# 02-FPGA_IO_MIPI_TS.net
KiCad netlist of a schematic drawn in Altium Designer
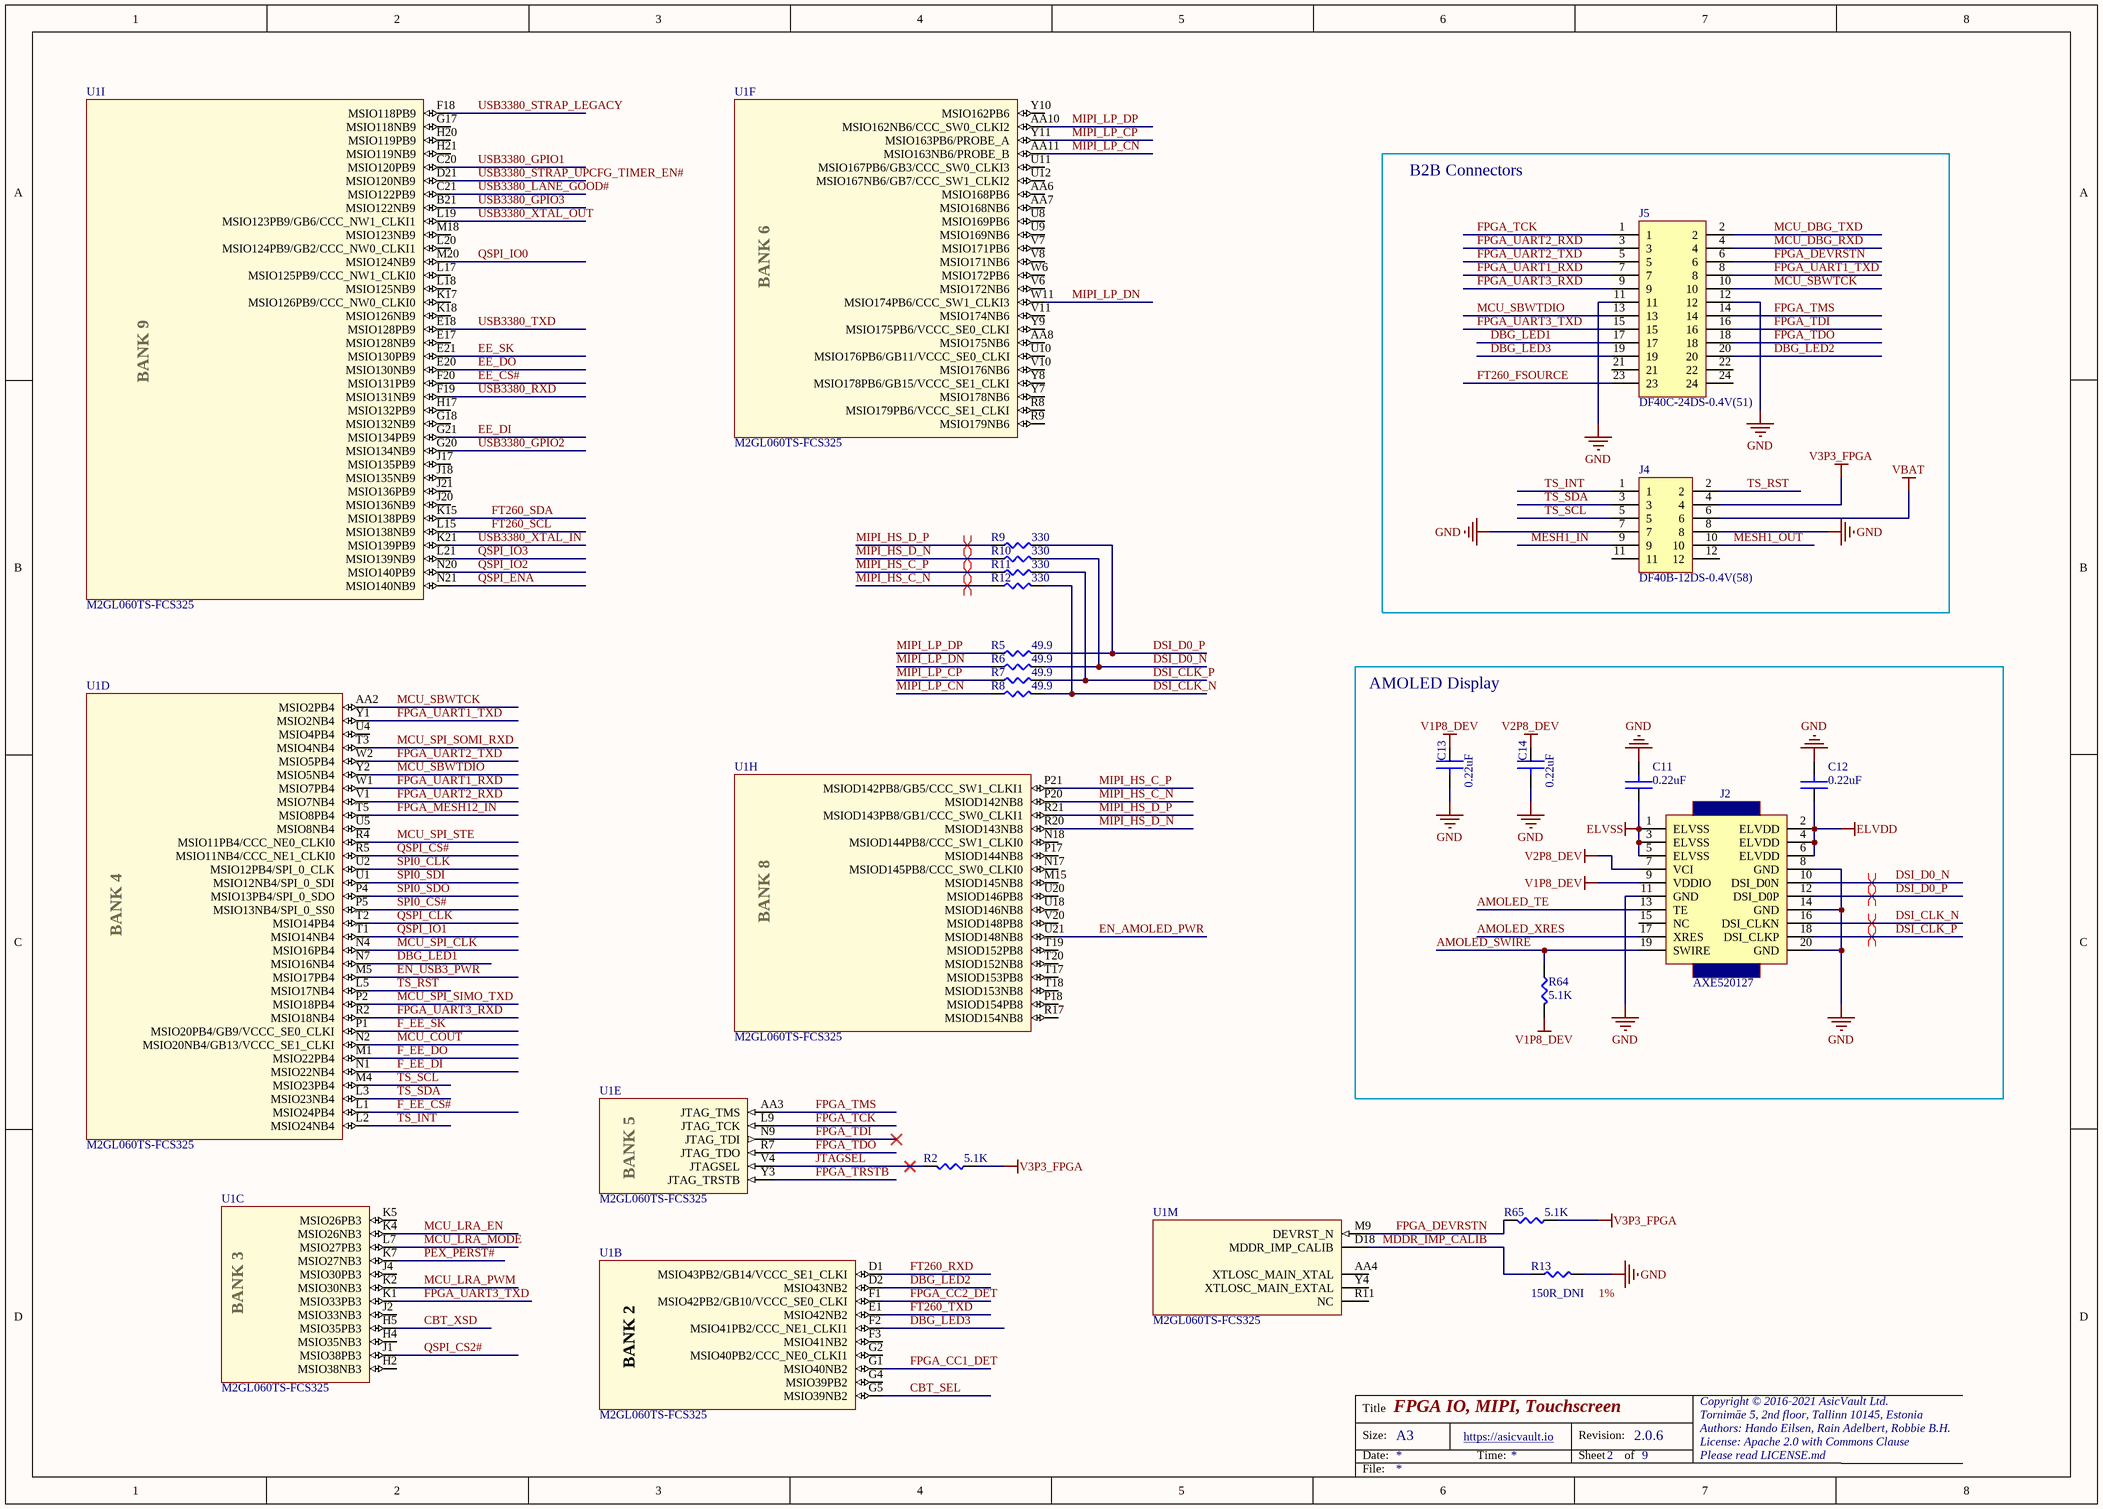
[diagram p0: 02-FPGA_IO_MIPI_TS.SchDoc]

(export (version "E")
  (design (tool "Eeschema 10.0.6"))
  (components
    (comp (ref "C11") (value "0.22uF") (footprint "C0201") (libsource (lib "AMOLED") (part "0.22uF/0201")))
    (comp (ref "C12") (value "0.22uF") (footprint "C0201") (libsource (lib "AMOLED") (part "0.22uF/0201")))
    (comp (ref "C13") (value "0.22uF") (footprint "C0201") (libsource (lib "AMOLED") (part "0.22uF/0201")))
    (comp (ref "C14") (value "0.22uF") (footprint "C0201") (libsource (lib "AMOLED") (part "0.22uF/0201")))
    (comp (ref "J2")
      (value "AXE520127")
      (footprint "AXE520127")
      (libsource (lib "AMOLED") (part "AXE520127"))
    )
    (comp (ref "J4")
      (value "DF40B-12DS-0.4V(58)")
      (footprint "DF40B-12DS")
      (libsource (lib "AMOLED") (part "DF40B-12DS-0.4V(58)"))
    )
    (comp (ref "J5")
      (value "DF40C-24DS-0.4V(51)")
      (footprint "DF40C-24DS")
      (libsource (lib "AMOLED") (part "DF40C-24DS-0.4V(51)"))
    )
    (comp (ref "R2")
      (value "5.1K")
      (footprint "R0201")
      (libsource (lib "Control_Board") (part "5.1K/1%/0201"))
    )
    (comp (ref "R5")
      (value "49.9")
      (footprint "R0201")
      (libsource (lib "Control_Board") (part "49.9/1%/0201"))
    )
    (comp (ref "R6")
      (value "49.9")
      (footprint "R0201")
      (libsource (lib "Control_Board") (part "49.9/1%/0201"))
    )
    (comp (ref "R7")
      (value "49.9")
      (footprint "R0201")
      (libsource (lib "Control_Board") (part "49.9/1%/0201"))
    )
    (comp (ref "R8")
      (value "49.9")
      (footprint "R0201")
      (libsource (lib "Control_Board") (part "49.9/1%/0201"))
    )
    (comp (ref "R9") (value "330") (footprint "R0201") (libsource (lib "Control_Board") (part "330/1%/0201")))
    (comp (ref "R10")
      (value "330")
      (footprint "R0201")
      (libsource (lib "Control_Board") (part "330/1%/0201"))
    )
    (comp (ref "R11")
      (value "330")
      (footprint "R0201")
      (libsource (lib "Control_Board") (part "330/1%/0201"))
    )
    (comp (ref "R12")
      (value "330")
      (footprint "R0201")
      (libsource (lib "Control_Board") (part "330/1%/0201"))
    )
    (comp (ref "R13")
      (value "150R_DNI")
      (footprint "R0201")
      (libsource (lib "Control_Board") (part "150R/1%/0201"))
    )
    (comp (ref "R64")
      (value "5.1K")
      (footprint "R0201")
      (libsource (lib "Control_Board") (part "5.1K/1%/0201"))
    )
    (comp (ref "R65")
      (value "5.1K")
      (footprint "R0201")
      (libsource (lib "Control_Board") (part "5.1K/1%/0201"))
    )
    (comp (ref "U1")
      (value "M2GL060TS-FCS325")
      (footprint "FCS325-OPT1")
      (libsource (lib "Board3") (part "M2GL060TS-FCS325"))
    )
  )
  (nets
    (net (code "1") (name "/AMOLED_SWIRE") (class "Default")
      (node (ref "J2") (pin "19") (pinfunction "SWIRE_19") (pintype "passive"))
      (node (ref "R64") (pin "1") (pinfunction "1_1") (pintype "passive"))
    )
    (net (code "2") (name "/AMOLED_TE") (class "Default")
      (node (ref "J2") (pin "13") (pinfunction "TE_13") (pintype "passive"))
    )
    (net (code "3") (name "/AMOLED_XRES") (class "Default")
      (node (ref "J2") (pin "17") (pinfunction "XRES_17") (pintype "passive"))
    )
    (net (code "4") (name "/CBT_SEL") (class "Default")
      (node (ref "U1") (pin "G5") (pinfunction "MSIO39NB2_G5") (pintype "bidirectional"))
    )
    (net (code "5") (name "/CBT_XSD") (class "Default")
      (node (ref "U1") (pin "H5") (pinfunction "MSIO35PB3_H5") (pintype "bidirectional"))
    )
    (net (code "6") (name "/DBG_LED1") (class "Default")
      (node (ref "J5") (pin "17") (pinfunction "17_17") (pintype "passive"))
      (node (ref "U1") (pin "N7") (pinfunction "MSIO16NB4_N7") (pintype "bidirectional"))
    )
    (net (code "7") (name "/DBG_LED2") (class "Default")
      (node (ref "J5") (pin "20") (pinfunction "20_20") (pintype "passive"))
      (node (ref "U1") (pin "D2") (pinfunction "MSIO43NB2_D2") (pintype "bidirectional"))
    )
    (net (code "8") (name "/DBG_LED3") (class "Default")
      (node (ref "J5") (pin "19") (pinfunction "19_19") (pintype "passive"))
      (node (ref "U1") (pin "F2") (pinfunction "MSIO41PB2/CCC_NE1_CLKI1_F2") (pintype "bidirectional"))
    )
    (net (code "9") (name "/DSI_CLK_N") (class "Default")
      (node (ref "J2") (pin "16") (pinfunction "DSI_CLKN_16") (pintype "passive"))
      (node (ref "R12") (pin "2") (pinfunction "2_2") (pintype "passive"))
      (node (ref "R8") (pin "2") (pinfunction "2_2") (pintype "passive"))
    )
    (net (code "10") (name "/DSI_CLK_P") (class "Default")
      (node (ref "J2") (pin "18") (pinfunction "DSI_CLKP_18") (pintype "passive"))
      (node (ref "R11") (pin "2") (pinfunction "2_2") (pintype "passive"))
      (node (ref "R7") (pin "2") (pinfunction "2_2") (pintype "passive"))
    )
    (net (code "11") (name "/DSI_D0_N") (class "Default")
      (node (ref "J2") (pin "10") (pinfunction "DSI_D0N_10") (pintype "passive"))
      (node (ref "R10") (pin "2") (pinfunction "2_2") (pintype "passive"))
      (node (ref "R6") (pin "2") (pinfunction "2_2") (pintype "passive"))
    )
    (net (code "12") (name "/DSI_D0_P") (class "Default")
      (node (ref "J2") (pin "12") (pinfunction "DSI_D0P_12") (pintype "passive"))
      (node (ref "R5") (pin "2") (pinfunction "2_2") (pintype "passive"))
      (node (ref "R9") (pin "2") (pinfunction "2_2") (pintype "passive"))
    )
    (net (code "13") (name "/EE_CS#") (class "Default")
      (node (ref "U1") (pin "F20") (pinfunction "MSIO131PB9_F20") (pintype "bidirectional"))
    )
    (net (code "14") (name "/EE_DI") (class "Default")
      (node (ref "U1") (pin "G21") (pinfunction "MSIO134PB9_G21") (pintype "bidirectional"))
    )
    (net (code "15") (name "/EE_DO") (class "Default")
      (node (ref "U1") (pin "E20") (pinfunction "MSIO130NB9_E20") (pintype "bidirectional"))
    )
    (net (code "16") (name "/EE_SK") (class "Default")
      (node (ref "U1") (pin "E21") (pinfunction "MSIO130PB9_E21") (pintype "bidirectional"))
    )
    (net (code "17") (name "/EN_AMOLED_PWR") (class "Default")
      (node (ref "U1") (pin "U21") (pinfunction "MSIOD148NB8_U21") (pintype "bidirectional"))
    )
    (net (code "18") (name "/EN_USB3_PWR") (class "Default")
      (node (ref "U1") (pin "M5") (pinfunction "MSIO17PB4_M5") (pintype "bidirectional"))
    )
    (net (code "19") (name "/FPGA_CC1_DET") (class "Default")
      (node (ref "U1") (pin "G1") (pinfunction "MSIO40NB2_G1") (pintype "bidirectional"))
    )
    (net (code "20") (name "/FPGA_CC2_DET") (class "Default")
      (node (ref "U1") (pin "F1") (pinfunction "MSIO42PB2/GB10/VCCC_SE0_CLKI_F1") (pintype "bidirectional"))
    )
    (net (code "21") (name "/FPGA_DEVRSTN") (class "Default")
      (node (ref "J5") (pin "6") (pinfunction "6_6") (pintype "passive"))
      (node (ref "R65") (pin "2") (pinfunction "2_2") (pintype "passive"))
      (node (ref "U1") (pin "M9") (pinfunction "DEVRST_N_M9") (pintype "input"))
    )
    (net (code "22") (name "/FPGA_MESH12_IN") (class "Default")
      (node (ref "U1") (pin "T5") (pinfunction "MSIO8PB4_T5") (pintype "bidirectional"))
    )
    (net (code "23") (name "/FPGA_TCK") (class "Default")
      (node (ref "J5") (pin "1") (pinfunction "1_1") (pintype "passive"))
      (node (ref "U1") (pin "L9") (pinfunction "JTAG_TCK_L9") (pintype "input"))
    )
    (net (code "24") (name "/FPGA_TDI") (class "Default")
      (node (ref "J5") (pin "16") (pinfunction "16_16") (pintype "passive"))
      (node (ref "U1") (pin "N9") (pinfunction "JTAG_TDI_N9") (pintype "output"))
    )
    (net (code "25") (name "/FPGA_TDO") (class "Default")
      (node (ref "J5") (pin "18") (pinfunction "18_18") (pintype "passive"))
      (node (ref "U1") (pin "R7") (pinfunction "JTAG_TDO_R7") (pintype "input"))
    )
    (net (code "26") (name "/FPGA_TMS") (class "Default")
      (node (ref "J5") (pin "14") (pinfunction "14_14") (pintype "passive"))
      (node (ref "U1") (pin "AA3") (pinfunction "JTAG_TMS_AA3") (pintype "input"))
    )
    (net (code "27") (name "/FPGA_TRSTB") (class "Default")
      (node (ref "U1") (pin "Y3") (pinfunction "JTAG_TRSTB_Y3") (pintype "input"))
    )
    (net (code "28") (name "/FPGA_UART1_RXD") (class "Default")
      (node (ref "J5") (pin "7") (pinfunction "7_7") (pintype "passive"))
      (node (ref "U1") (pin "W1") (pinfunction "MSIO7PB4_W1") (pintype "bidirectional"))
    )
    (net (code "29") (name "/FPGA_UART1_TXD") (class "Default")
      (node (ref "J5") (pin "8") (pinfunction "8_8") (pintype "passive"))
      (node (ref "U1") (pin "Y1") (pinfunction "MSIO2NB4_Y1") (pintype "bidirectional"))
    )
    (net (code "30") (name "/FPGA_UART2_RXD") (class "Default")
      (node (ref "J5") (pin "3") (pinfunction "3_3") (pintype "passive"))
      (node (ref "U1") (pin "V1") (pinfunction "MSIO7NB4_V1") (pintype "bidirectional"))
    )
    (net (code "31") (name "/FPGA_UART2_TXD") (class "Default")
      (node (ref "J5") (pin "5") (pinfunction "5_5") (pintype "passive"))
      (node (ref "U1") (pin "W2") (pinfunction "MSIO5PB4_W2") (pintype "bidirectional"))
    )
    (net (code "32") (name "/FPGA_UART3_RXD") (class "Default")
      (node (ref "J5") (pin "9") (pinfunction "9_9") (pintype "passive"))
      (node (ref "U1") (pin "R2") (pinfunction "MSIO18NB4_R2") (pintype "bidirectional"))
    )
    (net (code "33") (name "/FPGA_UART3_TXD") (class "Default")
      (node (ref "J5") (pin "15") (pinfunction "15_15") (pintype "passive"))
      (node (ref "U1") (pin "K1") (pinfunction "MSIO33PB3_K1") (pintype "bidirectional"))
    )
    (net (code "34") (name "/FT260_FSOURCE") (class "Default")
      (node (ref "J5") (pin "23") (pinfunction "23_23") (pintype "passive"))
    )
    (net (code "35") (name "/FT260_RXD") (class "Default")
      (node (ref "U1") (pin "D1") (pinfunction "MSIO43PB2/GB14/VCCC_SE1_CLKI_D1") (pintype "bidirectional"))
    )
    (net (code "36") (name "/FT260_SCL") (class "Default")
      (node (ref "U1") (pin "L15") (pinfunction "MSIO138NB9_L15") (pintype "bidirectional"))
    )
    (net (code "37") (name "/FT260_SDA") (class "Default")
      (node (ref "U1") (pin "K15") (pinfunction "MSIO138PB9_K15") (pintype "bidirectional"))
    )
    (net (code "38") (name "/FT260_TXD") (class "Default")
      (node (ref "U1") (pin "E1") (pinfunction "MSIO42NB2_E1") (pintype "bidirectional"))
    )
    (net (code "39") (name "/F_EE_CS#") (class "Default")
      (node (ref "U1") (pin "L1") (pinfunction "MSIO24PB4_L1") (pintype "bidirectional"))
    )
    (net (code "40") (name "/F_EE_DI") (class "Default")
      (node (ref "U1") (pin "N1") (pinfunction "MSIO22NB4_N1") (pintype "bidirectional"))
    )
    (net (code "41") (name "/F_EE_DO") (class "Default")
      (node (ref "U1") (pin "M1") (pinfunction "MSIO22PB4_M1") (pintype "bidirectional"))
    )
    (net (code "42") (name "/F_EE_SK") (class "Default")
      (node (ref "U1") (pin "P1") (pinfunction "MSIO20PB4/GB9/VCCC_SE0_CLKI_P1") (pintype "bidirectional"))
    )
    (net (code "43") (name "/JTAGSEL") (class "Default")
      (node (ref "R2") (pin "2") (pinfunction "2_2") (pintype "passive"))
      (node (ref "U1") (pin "V4") (pinfunction "JTAGSEL_V4") (pintype "input"))
    )
    (net (code "44") (name "/MCU_COUT") (class "Default")
      (node (ref "U1") (pin "N2") (pinfunction "MSIO20NB4/GB13/VCCC_SE1_CLKI_N2") (pintype "bidirectional"))
    )
    (net (code "45") (name "/MCU_DBG_RXD") (class "Default")
      (node (ref "J5") (pin "4") (pinfunction "4_4") (pintype "passive"))
    )
    (net (code "46") (name "/MCU_DBG_TXD") (class "Default")
      (node (ref "J5") (pin "2") (pinfunction "2_2") (pintype "passive"))
    )
    (net (code "47") (name "/MCU_LRA_EN") (class "Default")
      (node (ref "U1") (pin "K4") (pinfunction "MSIO26NB3_K4") (pintype "bidirectional"))
    )
    (net (code "48") (name "/MCU_LRA_MODE") (class "Default")
      (node (ref "U1") (pin "L7") (pinfunction "MSIO27PB3_L7") (pintype "bidirectional"))
    )
    (net (code "49") (name "/MCU_LRA_PWM") (class "Default")
      (node (ref "U1") (pin "K2") (pinfunction "MSIO30NB3_K2") (pintype "bidirectional"))
    )
    (net (code "50") (name "/MCU_SBWTCK") (class "Default")
      (node (ref "J5") (pin "10") (pinfunction "10_10") (pintype "passive"))
      (node (ref "U1") (pin "AA2") (pinfunction "MSIO2PB4_AA2") (pintype "bidirectional"))
    )
    (net (code "51") (name "/MCU_SBWTDIO") (class "Default")
      (node (ref "J5") (pin "13") (pinfunction "13_13") (pintype "passive"))
      (node (ref "U1") (pin "Y2") (pinfunction "MSIO5NB4_Y2") (pintype "bidirectional"))
    )
    (net (code "52") (name "/MCU_SPI_CLK") (class "Default")
      (node (ref "U1") (pin "N4") (pinfunction "MSIO16PB4_N4") (pintype "bidirectional"))
    )
    (net (code "53") (name "/MCU_SPI_SIMO_TXD") (class "Default")
      (node (ref "U1") (pin "P2") (pinfunction "MSIO18PB4_P2") (pintype "bidirectional"))
    )
    (net (code "54") (name "/MCU_SPI_SOMI_RXD") (class "Default")
      (node (ref "U1") (pin "T3") (pinfunction "MSIO4NB4_T3") (pintype "bidirectional"))
    )
    (net (code "55") (name "/MCU_SPI_STE") (class "Default")
      (node (ref "U1") (pin "R4") (pinfunction "MSIO11PB4/CCC_NE0_CLKI0_R4") (pintype "bidirectional"))
    )
    (net (code "56") (name "/MDDR_IMP_CALIB") (class "Default")
      (node (ref "R13") (pin "1") (pinfunction "1_1") (pintype "passive"))
      (node (ref "U1") (pin "D18") (pinfunction "MDDR_IMP_CALIB_D18") (pintype "passive"))
    )
    (net (code "57") (name "/MESH1_IN") (class "Default")
      (node (ref "J4") (pin "9") (pinfunction "9_9") (pintype "passive"))
    )
    (net (code "58") (name "/MESH1_OUT") (class "Default")
      (node (ref "J4") (pin "10") (pinfunction "10_10") (pintype "passive"))
    )
    (net (code "59") (name "/MIPI_HS_C_N") (class "Default")
      (node (ref "R12") (pin "1") (pinfunction "1_1") (pintype "passive"))
      (node (ref "U1") (pin "P20") (pinfunction "MSIOD142NB8_P20") (pintype "bidirectional"))
    )
    (net (code "60") (name "/MIPI_HS_C_P") (class "Default")
      (node (ref "R11") (pin "1") (pinfunction "1_1") (pintype "passive"))
      (node (ref "U1") (pin "P21") (pinfunction "MSIOD142PB8/GB5/CCC_SW1_CLKI1_P21") (pintype "bidirectional"))
    )
    (net (code "61") (name "/MIPI_HS_D_N") (class "Default")
      (node (ref "R10") (pin "1") (pinfunction "1_1") (pintype "passive"))
      (node (ref "U1") (pin "R20") (pinfunction "MSIOD143NB8_R20") (pintype "bidirectional"))
    )
    (net (code "62") (name "/MIPI_HS_D_P") (class "Default")
      (node (ref "R9") (pin "1") (pinfunction "1_1") (pintype "passive"))
      (node (ref "U1") (pin "R21") (pinfunction "MSIOD143PB8/GB1/CCC_SW0_CLKI1_R21") (pintype "bidirectional"))
    )
    (net (code "63") (name "/MIPI_LP_CN") (class "Default")
      (node (ref "R8") (pin "1") (pinfunction "1_1") (pintype "passive"))
      (node (ref "U1") (pin "AA11") (pinfunction "MSIO163NB6/PROBE_B_AA11") (pintype "bidirectional"))
    )
    (net (code "64") (name "/MIPI_LP_CP") (class "Default")
      (node (ref "R7") (pin "1") (pinfunction "1_1") (pintype "passive"))
      (node (ref "U1") (pin "Y11") (pinfunction "MSIO163PB6/PROBE_A_Y11") (pintype "bidirectional"))
    )
    (net (code "65") (name "/MIPI_LP_DN") (class "Default")
      (node (ref "R6") (pin "1") (pinfunction "1_1") (pintype "passive"))
      (node (ref "U1") (pin "W11") (pinfunction "MSIO174PB6/CCC_SW1_CLKI3_W11") (pintype "bidirectional"))
    )
    (net (code "66") (name "/MIPI_LP_DP") (class "Default")
      (node (ref "R5") (pin "1") (pinfunction "1_1") (pintype "passive"))
      (node (ref "U1") (pin "AA10") (pinfunction "MSIO162NB6/CCC_SW0_CLKI2_AA10") (pintype "bidirectional"))
    )
    (net (code "67") (name "/PEX_PERST#") (class "Default")
      (node (ref "U1") (pin "K7") (pinfunction "MSIO27NB3_K7") (pintype "bidirectional"))
    )
    (net (code "68") (name "/QSPI_CLK") (class "Default")
      (node (ref "U1") (pin "T2") (pinfunction "MSIO14PB4_T2") (pintype "bidirectional"))
    )
    (net (code "69") (name "/QSPI_CS#") (class "Default")
      (node (ref "U1") (pin "R5") (pinfunction "MSIO11NB4/CCC_NE1_CLKI0_R5") (pintype "bidirectional"))
    )
    (net (code "70") (name "/QSPI_CS2#") (class "Default")
      (node (ref "U1") (pin "J1") (pinfunction "MSIO38PB3_J1") (pintype "bidirectional"))
    )
    (net (code "71") (name "/QSPI_ENA") (class "Default")
      (node (ref "U1") (pin "N21") (pinfunction "MSIO140NB9_N21") (pintype "bidirectional"))
    )
    (net (code "72") (name "/QSPI_IO0") (class "Default")
      (node (ref "U1") (pin "M20") (pinfunction "MSIO124NB9_M20") (pintype "bidirectional"))
    )
    (net (code "73") (name "/QSPI_IO1") (class "Default")
      (node (ref "U1") (pin "T1") (pinfunction "MSIO14NB4_T1") (pintype "bidirectional"))
    )
    (net (code "74") (name "/QSPI_IO2") (class "Default")
      (node (ref "U1") (pin "N20") (pinfunction "MSIO140PB9_N20") (pintype "bidirectional"))
    )
    (net (code "75") (name "/QSPI_IO3") (class "Default")
      (node (ref "U1") (pin "L21") (pinfunction "MSIO139NB9_L21") (pintype "bidirectional"))
    )
    (net (code "76") (name "/SPI0_CLK") (class "Default")
      (node (ref "U1") (pin "U2") (pinfunction "MSIO12PB4/SPI_0_CLK_U2") (pintype "bidirectional"))
    )
    (net (code "77") (name "/SPI0_CS#") (class "Default")
      (node (ref "U1") (pin "P5") (pinfunction "MSIO13NB4/SPI_0_SS0_P5") (pintype "bidirectional"))
    )
    (net (code "78") (name "/SPI0_SDI") (class "Default")
      (node (ref "U1") (pin "U1") (pinfunction "MSIO12NB4/SPI_0_SDI_U1") (pintype "bidirectional"))
    )
    (net (code "79") (name "/SPI0_SDO") (class "Default")
      (node (ref "U1") (pin "P4") (pinfunction "MSIO13PB4/SPI_0_SDO_P4") (pintype "bidirectional"))
    )
    (net (code "80") (name "/TS_INT") (class "Default")
      (node (ref "J4") (pin "1") (pinfunction "1_1") (pintype "passive"))
      (node (ref "U1") (pin "L2") (pinfunction "MSIO24NB4_L2") (pintype "bidirectional"))
    )
    (net (code "81") (name "/TS_RST") (class "Default")
      (node (ref "J4") (pin "2") (pinfunction "2_2") (pintype "passive"))
      (node (ref "U1") (pin "L5") (pinfunction "MSIO17NB4_L5") (pintype "bidirectional"))
    )
    (net (code "82") (name "/TS_SCL") (class "Default")
      (node (ref "J4") (pin "5") (pinfunction "5_5") (pintype "passive"))
      (node (ref "U1") (pin "M4") (pinfunction "MSIO23PB4_M4") (pintype "bidirectional"))
    )
    (net (code "83") (name "/TS_SDA") (class "Default")
      (node (ref "J4") (pin "3") (pinfunction "3_3") (pintype "passive"))
      (node (ref "U1") (pin "L3") (pinfunction "MSIO23NB4_L3") (pintype "bidirectional"))
    )
    (net (code "84") (name "/USB3380_GPIO1") (class "Default")
      (node (ref "U1") (pin "C20") (pinfunction "MSIO120PB9_C20") (pintype "bidirectional"))
    )
    (net (code "85") (name "/USB3380_GPIO2") (class "Default")
      (node (ref "U1") (pin "G20") (pinfunction "MSIO134NB9_G20") (pintype "bidirectional"))
    )
    (net (code "86") (name "/USB3380_GPIO3") (class "Default")
      (node (ref "U1") (pin "B21") (pinfunction "MSIO122NB9_B21") (pintype "bidirectional"))
    )
    (net (code "87") (name "/USB3380_LANE_GOOD#") (class "Default")
      (node (ref "U1") (pin "C21") (pinfunction "MSIO122PB9_C21") (pintype "bidirectional"))
    )
    (net (code "88") (name "/USB3380_RXD") (class "Default")
      (node (ref "U1") (pin "F19") (pinfunction "MSIO131NB9_F19") (pintype "bidirectional"))
    )
    (net (code "89") (name "/USB3380_STRAP_LEGACY") (class "Default")
      (node (ref "U1") (pin "F18") (pinfunction "MSIO118PB9_F18") (pintype "bidirectional"))
    )
    (net (code "90") (name "/USB3380_STRAP_UPCFG_TIMER_EN#") (class "Default")
      (node (ref "U1") (pin "D21") (pinfunction "MSIO120NB9_D21") (pintype "bidirectional"))
    )
    (net (code "91") (name "/USB3380_TXD") (class "Default")
      (node (ref "U1") (pin "E18") (pinfunction "MSIO128PB9_E18") (pintype "bidirectional"))
    )
    (net (code "92") (name "/USB3380_XTAL_IN") (class "Default")
      (node (ref "U1") (pin "K21") (pinfunction "MSIO139PB9_K21") (pintype "bidirectional"))
    )
    (net (code "93") (name "/USB3380_XTAL_OUT") (class "Default")
      (node (ref "U1") (pin "L19") (pinfunction "MSIO123PB9/GB6/CCC_NW1_CLKI1_L19") (pintype "bidirectional"))
    )
    (net (code "94") (name "ELVDD") (class "Default")
      (node (ref "C12") (pin "1") (pinfunction "1_1") (pintype "passive"))
      (node (ref "J2") (pin "2") (pinfunction "ELVDD_2") (pintype "passive"))
      (node (ref "J2") (pin "4") (pinfunction "ELVDD_4") (pintype "passive"))
      (node (ref "J2") (pin "6") (pinfunction "ELVDD_6") (pintype "passive"))
    )
    (net (code "95") (name "ELVSS") (class "Default")
      (node (ref "C11") (pin "1") (pinfunction "1_1") (pintype "passive"))
      (node (ref "J2") (pin "1") (pinfunction "ELVSS_1") (pintype "passive"))
      (node (ref "J2") (pin "3") (pinfunction "ELVSS_3") (pintype "passive"))
      (node (ref "J2") (pin "5") (pinfunction "ELVSS_5") (pintype "passive"))
    )
    (net (code "96") (name "GND") (class "Default")
      (node (ref "C11") (pin "2") (pinfunction "2_2") (pintype "passive"))
      (node (ref "C12") (pin "2") (pinfunction "2_2") (pintype "passive"))
      (node (ref "C13") (pin "2") (pinfunction "2_2") (pintype "passive"))
      (node (ref "C14") (pin "2") (pinfunction "2_2") (pintype "passive"))
      (node (ref "J2") (pin "11") (pinfunction "GND_11") (pintype "passive"))
      (node (ref "J2") (pin "14") (pinfunction "GND_14") (pintype "passive"))
      (node (ref "J2") (pin "20") (pinfunction "GND_20") (pintype "passive"))
      (node (ref "J2") (pin "8") (pinfunction "GND_8") (pintype "passive"))
      (node (ref "J4") (pin "7") (pinfunction "7_7") (pintype "passive"))
      (node (ref "J4") (pin "8") (pinfunction "8_8") (pintype "passive"))
      (node (ref "J5") (pin "11") (pinfunction "11_11") (pintype "passive"))
      (node (ref "J5") (pin "12") (pinfunction "12_12") (pintype "passive"))
      (node (ref "R13") (pin "2") (pinfunction "2_2") (pintype "passive"))
    )
    (net (code "97") (name "V1P8_DEV") (class "Default")
      (node (ref "C13") (pin "1") (pinfunction "1_1") (pintype "passive"))
      (node (ref "J2") (pin "9") (pinfunction "VDDIO_9") (pintype "passive"))
      (node (ref "R64") (pin "2") (pinfunction "2_2") (pintype "passive"))
    )
    (net (code "98") (name "V2P8_DEV") (class "Default")
      (node (ref "C14") (pin "1") (pinfunction "1_1") (pintype "passive"))
      (node (ref "J2") (pin "7") (pinfunction "VCI_7") (pintype "passive"))
    )
    (net (code "99") (name "V3P3_FPGA") (class "Default")
      (node (ref "J4") (pin "4") (pinfunction "4_4") (pintype "passive"))
      (node (ref "R2") (pin "1") (pinfunction "1_1") (pintype "passive"))
      (node (ref "R65") (pin "1") (pinfunction "1_1") (pintype "passive"))
    )
    (net (code "100") (name "VBAT") (class "Default")
      (node (ref "J4") (pin "6") (pinfunction "6_6") (pintype "passive"))
    )
    (net (code "101") (name "unconnected-(J2-NC-Pad15)") (class "Default")
      (node (ref "J2") (pin "15") (pinfunction "NC_15") (pintype "passive"))
    )
    (net (code "102") (name "unconnected-(J4-Pad11)") (class "Default")
      (node (ref "J4") (pin "11") (pinfunction "11_11") (pintype "passive"))
    )
    (net (code "103") (name "unconnected-(J4-Pad12)") (class "Default")
      (node (ref "J4") (pin "12") (pinfunction "12_12") (pintype "passive"))
    )
    (net (code "104") (name "unconnected-(J5-Pad21)") (class "Default")
      (node (ref "J5") (pin "21") (pinfunction "21_21") (pintype "passive"))
    )
    (net (code "105") (name "unconnected-(J5-Pad22)") (class "Default")
      (node (ref "J5") (pin "22") (pinfunction "22_22") (pintype "passive"))
    )
    (net (code "106") (name "unconnected-(J5-Pad24)") (class "Default")
      (node (ref "J5") (pin "24") (pinfunction "24_24") (pintype "passive"))
    )
    (net (code "107") (name "unconnected-(U1B-MSIO39PB2-PadG4)") (class "Default")
      (node (ref "U1") (pin "G4") (pinfunction "MSIO39PB2_G4") (pintype "bidirectional"))
    )
    (net (code "108") (name "unconnected-(U1B-MSIO40PB2{slash}CCC_NE0_CLKI1-PadG2)") (class "Default")
      (node (ref "U1") (pin "G2") (pinfunction "MSIO40PB2/CCC_NE0_CLKI1_G2") (pintype "bidirectional"))
    )
    (net (code "109") (name "unconnected-(U1B-MSIO41NB2-PadF3)") (class "Default")
      (node (ref "U1") (pin "F3") (pinfunction "MSIO41NB2_F3") (pintype "bidirectional"))
    )
    (net (code "110") (name "unconnected-(U1C-MSIO26PB3-PadK5)") (class "Default")
      (node (ref "U1") (pin "K5") (pinfunction "MSIO26PB3_K5") (pintype "bidirectional"))
    )
    (net (code "111") (name "unconnected-(U1C-MSIO30PB3-PadJ4)") (class "Default")
      (node (ref "U1") (pin "J4") (pinfunction "MSIO30PB3_J4") (pintype "bidirectional"))
    )
    (net (code "112") (name "unconnected-(U1C-MSIO33NB3-PadJ2)") (class "Default")
      (node (ref "U1") (pin "J2") (pinfunction "MSIO33NB3_J2") (pintype "bidirectional"))
    )
    (net (code "113") (name "unconnected-(U1C-MSIO35NB3-PadH4)") (class "Default")
      (node (ref "U1") (pin "H4") (pinfunction "MSIO35NB3_H4") (pintype "bidirectional"))
    )
    (net (code "114") (name "unconnected-(U1C-MSIO38NB3-PadH2)") (class "Default")
      (node (ref "U1") (pin "H2") (pinfunction "MSIO38NB3_H2") (pintype "bidirectional"))
    )
    (net (code "115") (name "unconnected-(U1D-MSIO4PB4-PadU4)") (class "Default")
      (node (ref "U1") (pin "U4") (pinfunction "MSIO4PB4_U4") (pintype "bidirectional"))
    )
    (net (code "116") (name "unconnected-(U1D-MSIO8NB4-PadU5)") (class "Default")
      (node (ref "U1") (pin "U5") (pinfunction "MSIO8NB4_U5") (pintype "bidirectional"))
    )
    (net (code "117") (name "unconnected-(U1F-MSIO162PB6-PadY10)") (class "Default")
      (node (ref "U1") (pin "Y10") (pinfunction "MSIO162PB6_Y10") (pintype "bidirectional"))
    )
    (net (code "118") (name "unconnected-(U1F-MSIO167NB6{slash}GB7{slash}CCC_SW1_CLKI2-PadU12)") (class "Default")
      (node (ref "U1") (pin "U12") (pinfunction "MSIO167NB6/GB7/CCC_SW1_CLKI2_U12") (pintype "bidirectional"))
    )
    (net (code "119") (name "unconnected-(U1F-MSIO167PB6{slash}GB3{slash}CCC_SW0_CLKI3-PadU11)") (class "Default")
      (node (ref "U1") (pin "U11") (pinfunction "MSIO167PB6/GB3/CCC_SW0_CLKI3_U11") (pintype "bidirectional"))
    )
    (net (code "120") (name "unconnected-(U1F-MSIO168NB6-PadAA7)") (class "Default")
      (node (ref "U1") (pin "AA7") (pinfunction "MSIO168NB6_AA7") (pintype "bidirectional"))
    )
    (net (code "121") (name "unconnected-(U1F-MSIO168PB6-PadAA6)") (class "Default")
      (node (ref "U1") (pin "AA6") (pinfunction "MSIO168PB6_AA6") (pintype "bidirectional"))
    )
    (net (code "122") (name "unconnected-(U1F-MSIO169NB6-PadU9)") (class "Default")
      (node (ref "U1") (pin "U9") (pinfunction "MSIO169NB6_U9") (pintype "bidirectional"))
    )
    (net (code "123") (name "unconnected-(U1F-MSIO169PB6-PadU8)") (class "Default")
      (node (ref "U1") (pin "U8") (pinfunction "MSIO169PB6_U8") (pintype "bidirectional"))
    )
    (net (code "124") (name "unconnected-(U1F-MSIO171NB6-PadV8)") (class "Default")
      (node (ref "U1") (pin "V8") (pinfunction "MSIO171NB6_V8") (pintype "bidirectional"))
    )
    (net (code "125") (name "unconnected-(U1F-MSIO171PB6-PadV7)") (class "Default")
      (node (ref "U1") (pin "V7") (pinfunction "MSIO171PB6_V7") (pintype "bidirectional"))
    )
    (net (code "126") (name "unconnected-(U1F-MSIO172NB6-PadV6)") (class "Default")
      (node (ref "U1") (pin "V6") (pinfunction "MSIO172NB6_V6") (pintype "bidirectional"))
    )
    (net (code "127") (name "unconnected-(U1F-MSIO172PB6-PadW6)") (class "Default")
      (node (ref "U1") (pin "W6") (pinfunction "MSIO172PB6_W6") (pintype "bidirectional"))
    )
    (net (code "128") (name "unconnected-(U1F-MSIO174NB6-PadV11)") (class "Default")
      (node (ref "U1") (pin "V11") (pinfunction "MSIO174NB6_V11") (pintype "bidirectional"))
    )
    (net (code "129") (name "unconnected-(U1F-MSIO175NB6-PadAA8)") (class "Default")
      (node (ref "U1") (pin "AA8") (pinfunction "MSIO175NB6_AA8") (pintype "bidirectional"))
    )
    (net (code "130") (name "unconnected-(U1F-MSIO175PB6{slash}VCCC_SE0_CLKI-PadY9)") (class "Default")
      (node (ref "U1") (pin "Y9") (pinfunction "MSIO175PB6/VCCC_SE0_CLKI_Y9") (pintype "bidirectional"))
    )
    (net (code "131") (name "unconnected-(U1F-MSIO176NB6-PadV10)") (class "Default")
      (node (ref "U1") (pin "V10") (pinfunction "MSIO176NB6_V10") (pintype "bidirectional"))
    )
    (net (code "132") (name "unconnected-(U1F-MSIO176PB6{slash}GB11{slash}VCCC_SE0_CLKI-PadU10)") (class "Default")
      (node (ref "U1") (pin "U10") (pinfunction "MSIO176PB6/GB11/VCCC_SE0_CLKI_U10") (pintype "bidirectional"))
    )
    (net (code "133") (name "unconnected-(U1F-MSIO178NB6-PadY7)") (class "Default")
      (node (ref "U1") (pin "Y7") (pinfunction "MSIO178NB6_Y7") (pintype "bidirectional"))
    )
    (net (code "134") (name "unconnected-(U1F-MSIO178PB6{slash}GB15{slash}VCCC_SE1_CLKI-PadY8)") (class "Default")
      (node (ref "U1") (pin "Y8") (pinfunction "MSIO178PB6/GB15/VCCC_SE1_CLKI_Y8") (pintype "bidirectional"))
    )
    (net (code "135") (name "unconnected-(U1F-MSIO179NB6-PadR9)") (class "Default")
      (node (ref "U1") (pin "R9") (pinfunction "MSIO179NB6_R9") (pintype "bidirectional"))
    )
    (net (code "136") (name "unconnected-(U1F-MSIO179PB6{slash}VCCC_SE1_CLKI-PadR8)") (class "Default")
      (node (ref "U1") (pin "R8") (pinfunction "MSIO179PB6/VCCC_SE1_CLKI_R8") (pintype "bidirectional"))
    )
    (net (code "137") (name "unconnected-(U1H-MSIOD144NB8-PadP17)") (class "Default")
      (node (ref "U1") (pin "P17") (pinfunction "MSIOD144NB8_P17") (pintype "bidirectional"))
    )
    (net (code "138") (name "unconnected-(U1H-MSIOD144PB8{slash}CCC_SW1_CLKI0-PadN18)") (class "Default")
      (node (ref "U1") (pin "N18") (pinfunction "MSIOD144PB8/CCC_SW1_CLKI0_N18") (pintype "bidirectional"))
    )
    (net (code "139") (name "unconnected-(U1H-MSIOD145NB8-PadM15)") (class "Default")
      (node (ref "U1") (pin "M15") (pinfunction "MSIOD145NB8_M15") (pintype "bidirectional"))
    )
    (net (code "140") (name "unconnected-(U1H-MSIOD145PB8{slash}CCC_SW0_CLKI0-PadN17)") (class "Default")
      (node (ref "U1") (pin "N17") (pinfunction "MSIOD145PB8/CCC_SW0_CLKI0_N17") (pintype "bidirectional"))
    )
    (net (code "141") (name "unconnected-(U1H-MSIOD146NB8-PadU18)") (class "Default")
      (node (ref "U1") (pin "U18") (pinfunction "MSIOD146NB8_U18") (pintype "bidirectional"))
    )
    (net (code "142") (name "unconnected-(U1H-MSIOD146PB8-PadU20)") (class "Default")
      (node (ref "U1") (pin "U20") (pinfunction "MSIOD146PB8_U20") (pintype "bidirectional"))
    )
    (net (code "143") (name "unconnected-(U1H-MSIOD148PB8-PadV20)") (class "Default")
      (node (ref "U1") (pin "V20") (pinfunction "MSIOD148PB8_V20") (pintype "bidirectional"))
    )
    (net (code "144") (name "unconnected-(U1H-MSIOD152NB8-PadT20)") (class "Default")
      (node (ref "U1") (pin "T20") (pinfunction "MSIOD152NB8_T20") (pintype "bidirectional"))
    )
    (net (code "145") (name "unconnected-(U1H-MSIOD152PB8-PadT19)") (class "Default")
      (node (ref "U1") (pin "T19") (pinfunction "MSIOD152PB8_T19") (pintype "bidirectional"))
    )
    (net (code "146") (name "unconnected-(U1H-MSIOD153NB8-PadT18)") (class "Default")
      (node (ref "U1") (pin "T18") (pinfunction "MSIOD153NB8_T18") (pintype "bidirectional"))
    )
    (net (code "147") (name "unconnected-(U1H-MSIOD153PB8-PadT17)") (class "Default")
      (node (ref "U1") (pin "T17") (pinfunction "MSIOD153PB8_T17") (pintype "bidirectional"))
    )
    (net (code "148") (name "unconnected-(U1H-MSIOD154NB8-PadR17)") (class "Default")
      (node (ref "U1") (pin "R17") (pinfunction "MSIOD154NB8_R17") (pintype "bidirectional"))
    )
    (net (code "149") (name "unconnected-(U1H-MSIOD154PB8-PadP18)") (class "Default")
      (node (ref "U1") (pin "P18") (pinfunction "MSIOD154PB8_P18") (pintype "bidirectional"))
    )
    (net (code "150") (name "unconnected-(U1I-MSIO118NB9-PadG17)") (class "Default")
      (node (ref "U1") (pin "G17") (pinfunction "MSIO118NB9_G17") (pintype "bidirectional"))
    )
    (net (code "151") (name "unconnected-(U1I-MSIO119NB9-PadH21)") (class "Default")
      (node (ref "U1") (pin "H21") (pinfunction "MSIO119NB9_H21") (pintype "bidirectional"))
    )
    (net (code "152") (name "unconnected-(U1I-MSIO119PB9-PadH20)") (class "Default")
      (node (ref "U1") (pin "H20") (pinfunction "MSIO119PB9_H20") (pintype "bidirectional"))
    )
    (net (code "153") (name "unconnected-(U1I-MSIO123NB9-PadM18)") (class "Default")
      (node (ref "U1") (pin "M18") (pinfunction "MSIO123NB9_M18") (pintype "bidirectional"))
    )
    (net (code "154") (name "unconnected-(U1I-MSIO124PB9{slash}GB2{slash}CCC_NW0_CLKI1-PadL20)") (class "Default")
      (node (ref "U1") (pin "L20") (pinfunction "MSIO124PB9/GB2/CCC_NW0_CLKI1_L20") (pintype "bidirectional"))
    )
    (net (code "155") (name "unconnected-(U1I-MSIO125NB9-PadL18)") (class "Default")
      (node (ref "U1") (pin "L18") (pinfunction "MSIO125NB9_L18") (pintype "bidirectional"))
    )
    (net (code "156") (name "unconnected-(U1I-MSIO125PB9{slash}CCC_NW1_CLKI0-PadL17)") (class "Default")
      (node (ref "U1") (pin "L17") (pinfunction "MSIO125PB9/CCC_NW1_CLKI0_L17") (pintype "bidirectional"))
    )
    (net (code "157") (name "unconnected-(U1I-MSIO126NB9-PadK18)") (class "Default")
      (node (ref "U1") (pin "K18") (pinfunction "MSIO126NB9_K18") (pintype "bidirectional"))
    )
    (net (code "158") (name "unconnected-(U1I-MSIO126PB9{slash}CCC_NW0_CLKI0-PadK17)") (class "Default")
      (node (ref "U1") (pin "K17") (pinfunction "MSIO126PB9/CCC_NW0_CLKI0_K17") (pintype "bidirectional"))
    )
    (net (code "159") (name "unconnected-(U1I-MSIO128NB9-PadE17)") (class "Default")
      (node (ref "U1") (pin "E17") (pinfunction "MSIO128NB9_E17") (pintype "bidirectional"))
    )
    (net (code "160") (name "unconnected-(U1I-MSIO132NB9-PadG18)") (class "Default")
      (node (ref "U1") (pin "G18") (pinfunction "MSIO132NB9_G18") (pintype "bidirectional"))
    )
    (net (code "161") (name "unconnected-(U1I-MSIO132PB9-PadH17)") (class "Default")
      (node (ref "U1") (pin "H17") (pinfunction "MSIO132PB9_H17") (pintype "bidirectional"))
    )
    (net (code "162") (name "unconnected-(U1I-MSIO135NB9-PadJ18)") (class "Default")
      (node (ref "U1") (pin "J18") (pinfunction "MSIO135NB9_J18") (pintype "bidirectional"))
    )
    (net (code "163") (name "unconnected-(U1I-MSIO135PB9-PadJ17)") (class "Default")
      (node (ref "U1") (pin "J17") (pinfunction "MSIO135PB9_J17") (pintype "bidirectional"))
    )
    (net (code "164") (name "unconnected-(U1I-MSIO136NB9-PadJ20)") (class "Default")
      (node (ref "U1") (pin "J20") (pinfunction "MSIO136NB9_J20") (pintype "bidirectional"))
    )
    (net (code "165") (name "unconnected-(U1I-MSIO136PB9-PadJ21)") (class "Default")
      (node (ref "U1") (pin "J21") (pinfunction "MSIO136PB9_J21") (pintype "bidirectional"))
    )
    (net (code "166") (name "unconnected-(U1M-NC-PadR11)") (class "Default")
      (node (ref "U1") (pin "R11") (pinfunction "NC_R11") (pintype "passive"))
    )
    (net (code "167") (name "unconnected-(U1M-XTLOSC_MAIN_EXTAL-PadY4)") (class "Default")
      (node (ref "U1") (pin "Y4") (pinfunction "XTLOSC_MAIN_EXTAL_Y4") (pintype "passive"))
    )
    (net (code "168") (name "unconnected-(U1M-XTLOSC_MAIN_XTAL-PadAA4)") (class "Default")
      (node (ref "U1") (pin "AA4") (pinfunction "XTLOSC_MAIN_XTAL_AA4") (pintype "passive"))
    )
  )
)
